# MCU_IO.net
KiCad netlist of a schematic drawn in Altium Designer
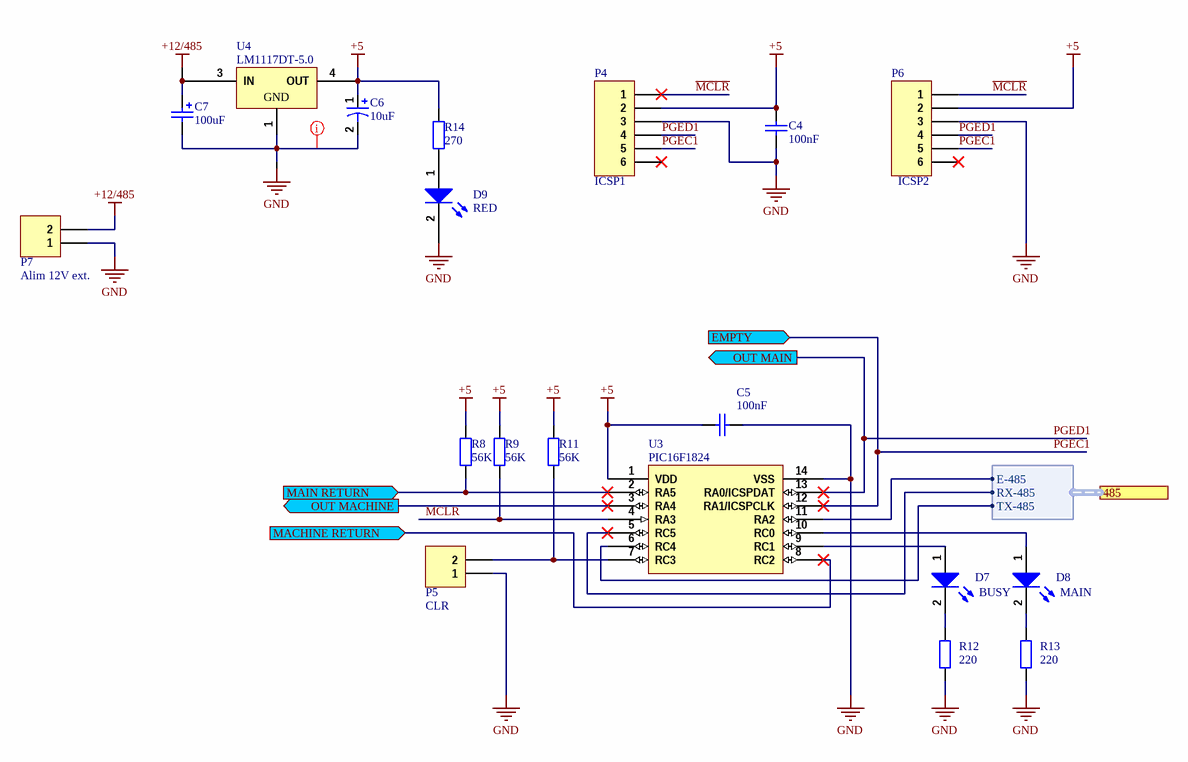
[diagram p0: MCU IO.SchDoc]

(export (version "E")
  (design (tool "Eeschema 10.0.6"))
  (components
    (comp (ref "C4")
      (value "100nF")
      (footprint "SYLANN:C0805")
      (description "Capacitor")
      (fields
        (field (name "MANUFACTURER") "MULTICOMP")
        (field (name "MANUFACTURER PART NUMBER") "MCCA000296")
      )
      (libsource (lib "Capacitors") (part "Cap 0805 100nF"))
    )
    (comp (ref "C5")
      (value "100nF")
      (footprint "SYLANN:C0805")
      (description "Capacitor")
      (fields
        (field (name "MANUFACTURER") "MULTICOMP")
        (field (name "MANUFACTURER PART NUMBER") "MCCA000296")
      )
      (libsource (lib "BRA") (part "Cap 0805 100nF"))
    )
    (comp (ref "C6")
      (value "10uF")
      (footprint "SYLANN:KEMET_4")
      (description "Polarized Capacitor")
      (fields
        (field (name "MANUFACTURER") "KEMET")
        (field (name "MANUFACTURER PART NUMBER") "EXV106M025A9BAA")
      )
      (libsource (lib "Miscellaneous Devices") (part "Cap Pol1"))
    )
    (comp (ref "C7")
      (value "100uF")
      (footprint "SYLANN:Kemet_63")
      (description "Polarized Capacitor")
      (fields
        (field (name "MANUFACTURER") "EPCOS")
        (field (name "MANUFACTURER PART NUMBER") "B41142A4107M")
        (field (name "HAUTEUR") "7.7")
        (field (name "LONGUEUR/HAUTEUR") "7.7")
      )
      (libsource (lib "BRA") (part "Cap Pol 100uF"))
    )
    (comp (ref "D7")
      (value "HSMH-C190")
      (footprint "0603-LEDR")
      (description "Surface Mount Chip LED, Red")
      (fields
        (field (name "MANUFACTURER") "AVAGO TECHNOLOGIES")
        (field (name "MANUFACTURER PART NUMBER") "HSMH-C190.")
        (field (name "INDICATOR") "BUSY")
        (field (name "LONGUEUR/HAUTEUR") "1.6")
      )
      (libsource (lib "BRA") (part "HSMH-C190"))
    )
    (comp (ref "D8")
      (value "HSMH-C190")
      (footprint "0603-LEDV")
      (description "Surface Mount Chip LED, Red")
      (fields
        (field (name "MANUFACTURER") "AVAGO TECHNOLOGIES")
        (field (name "MANUFACTURER PART NUMBER") "HSMH-C190.")
        (field (name "INDICATOR") "MAIN")
        (field (name "LONGUEUR/HAUTEUR") "1.6")
      )
      (libsource (lib "BRA") (part "HSMH-C190"))
    )
    (comp (ref "D9")
      (value "HSMH-C190")
      (footprint "0603-LEDR")
      (description "Surface Mount Chip LED, Red")
      (fields
        (field (name "MANUFACTURER") "AVAGO TECHNOLOGIES")
        (field (name "MANUFACTURER PART NUMBER") "HSMH-C190.")
        (field (name "COULEUR") "RED")
        (field (name "LONGUEUR/HAUTEUR") "1.6")
      )
      (libsource (lib "Avago Optoelectronic LED") (part "HSMH-C190"))
    )
    (comp (ref "P4")
      (value "ICSP1")
      (footprint "TC2030")
      (description "Header, 6-Pin")
      (fields (field (name "MANUFACTURER") "HARWIN") (field (name "MANUFACTURER PART NUMBER") "M20-8770642"))
      (libsource (lib "Miscellaneous Connectors") (part "Header 6"))
    )
    (comp (ref "P5")
      (value "CLR")
      (footprint "SYLANN:M20_1X2")
      (description "Header, 2-Pin")
      (fields
        (field (name "MANUFACTURER") "HARWIN")
        (field (name "MANUFACTURER PART NUMBER") "M20-8770242")
        (field (name "PUBLISHER") "Altium Limited")
      )
      (libsource (lib "Miscellaneous Connectors") (part "Header 2"))
    )
    (comp (ref "P6")
      (value "ICSP2")
      (footprint "6SIP100")
      (description "Header, 6-Pin")
      (fields
        (field (name "MANUFACTURER") "TE CONNECTIVITY / AMP")
        (field (name "MANUFACTURER PART NUMBER") "4-103321-8.")
      )
      (libsource (lib "Miscellaneous Connectors") (part "Header 6"))
    )
    (comp (ref "P7")
      (value "Alim 12V ext.")
      (footprint "CO2P508")
      (description "Header, 2-Pin")
      (libsource (lib "Miscellaneous Connectors") (part "Header 2"))
    )
    (comp (ref "R8")
      (value "56K")
      (footprint "R0805")
      (description "Resistor")
      (fields
        (field (name "MANUFACTURER") "MULTICOMP")
        (field (name "MANUFACTURER PART NUMBER") "MC0.1W08051%56KFR")
      )
      (libsource (lib "BRA") (part "Resistor 0805 56K"))
    )
    (comp (ref "R9")
      (value "56K")
      (footprint "R0805")
      (description "Resistor")
      (fields
        (field (name "MANUFACTURER") "MULTICOMP")
        (field (name "MANUFACTURER PART NUMBER") "MC0.1W08051%56KFR")
      )
      (libsource (lib "BRA") (part "Resistor 0805 56K"))
    )
    (comp (ref "R11")
      (value "56K")
      (footprint "R0805")
      (description "Resistor")
      (fields
        (field (name "MANUFACTURER") "MULTICOMP")
        (field (name "MANUFACTURER PART NUMBER") "MC0.1W08051%56KFR")
      )
      (libsource (lib "BRA") (part "Resistor 0805 56K"))
    )
    (comp (ref "R12")
      (value "220")
      (footprint "R0805")
      (description "Resistor")
      (fields
        (field (name "MANUFACTURER") "MULTICOMP")
        (field (name "MANUFACTURER PART NUMBER") "MC01W08051220R")
      )
      (libsource (lib "BRA") (part "Resistor 0805 220"))
    )
    (comp (ref "R13")
      (value "220")
      (footprint "R0805")
      (description "Resistor")
      (fields
        (field (name "MANUFACTURER") "MULTICOMP")
        (field (name "MANUFACTURER PART NUMBER") "MC01W08051220R")
      )
      (libsource (lib "BRA") (part "Resistor 0805 220"))
    )
    (comp (ref "R14")
      (value "270")
      (footprint "R0805")
      (description "Resistor")
      (fields
        (field (name "MANUFACTURER") "MULTICOMP")
        (field (name "MANUFACTURER PART NUMBER") "MC0.1W08051%1KFR")
      )
      (libsource (lib "BRA") (part "Resistor 0805 1K"))
    )
    (comp (ref "U3")
      (value "PIC16F1824")
      (footprint "so-14")
      (description "14 Pin Flash Microcontrollers with XLP Technology")
      (fields
        (field (name "MANUFACTURER") "MICROCHIP")
        (field (name "MANUFACTURER PART NUMBER") "PIC16F1824-I/SL")
      )
      (libsource (lib "BRA") (part "PIC16(L)F1824"))
    )
    (comp (ref "U4")
      (value "LM1117DT-5.0")
      (footprint "SOT223")
      (description "800mA Low-Dropout Linear Regulator, 3-pin TO-252")
      (fields
        (field (name "MANUFACTURER") "TEXAS INSTRUMENTS")
        (field (name "MANUFACTURER PART NUMBER") "LM1117MP-5.0")
      )
      (libsource (lib "NSC LDO") (part "LM1117DT-5.0"))
    )
  )
  (nets
    (net (code "2") (name "+5") (class "Default")
      (node (ref "C4") (pin "2") (pinfunction "2_2") (pintype "passive"))
      (node (ref "C5") (pin "2") (pinfunction "2_2") (pintype "passive"))
      (node (ref "C6") (pin "1") (pinfunction "1_1") (pintype "passive"))
      (node (ref "P4") (pin "2") (pinfunction "2_2") (pintype "passive"))
      (node (ref "P6") (pin "2") (pinfunction "2_2") (pintype "passive"))
      (node (ref "R11") (pin "2") (pinfunction "2_2") (pintype "passive"))
      (node (ref "R14") (pin "2") (pinfunction "2_2") (pintype "passive"))
      (node (ref "R8") (pin "2") (pinfunction "2_2") (pintype "passive"))
      (node (ref "R9") (pin "2") (pinfunction "2_2") (pintype "passive"))
      (node (ref "U3") (pin "1") (pinfunction "VDD_1") (pintype "power_in"))
      (node (ref "U4") (pin "4") (pinfunction "OUT_4") (pintype "power_in"))
    )
    (net (code "3") (name "+12{slash}485") (class "Default")
      (node (ref "C7") (pin "1") (pinfunction "1_1") (pintype "passive"))
      (node (ref "P7") (pin "2") (pinfunction "2_2") (pintype "passive"))
      (node (ref "U4") (pin "3") (pinfunction "IN_3") (pintype "power_in"))
    )
    (net (code "4") (name "/E-485") (class "Default")
      (node (ref "U3") (pin "11") (pinfunction "RA2_11") (pintype "bidirectional"))
    )
    (net (code "5") (name "/MACHINE RETURN") (class "Default")
      (node (ref "U3") (pin "8") (pinfunction "RC2_8") (pintype "bidirectional+no_connect"))
    )
    (net (code "6") (name "/MAIN RETURN") (class "Default")
      (node (ref "R8") (pin "1") (pinfunction "1_1") (pintype "passive"))
      (node (ref "U3") (pin "2") (pinfunction "RA5_2") (pintype "bidirectional"))
    )
    (net (code "7") (name "/OUT MACHINE") (class "Default")
      (node (ref "U3") (pin "3") (pinfunction "RA4_3") (pintype "bidirectional+no_connect"))
    )
    (net (code "8") (name "/PGEC1") (class "Default")
      (node (ref "P4") (pin "5") (pinfunction "5_5") (pintype "passive"))
      (node (ref "P6") (pin "5") (pinfunction "5_5") (pintype "passive"))
      (node (ref "U3") (pin "12") (pinfunction "RA1/ICSPCLK_12") (pintype "bidirectional"))
    )
    (net (code "9") (name "/PGED1") (class "Default")
      (node (ref "P4") (pin "4") (pinfunction "4_4") (pintype "passive"))
      (node (ref "P6") (pin "4") (pinfunction "4_4") (pintype "passive"))
      (node (ref "U3") (pin "13") (pinfunction "RA0/ICSPDAT_13") (pintype "bidirectional"))
    )
    (net (code "10") (name "/RX-485") (class "Default")
      (node (ref "U3") (pin "5") (pinfunction "RC5_5") (pintype "bidirectional+no_connect"))
    )
    (net (code "11") (name "/TX-485") (class "Default")
      (node (ref "U3") (pin "6") (pinfunction "RC4_6") (pintype "bidirectional"))
    )
    (net (code "13") (name "/~{MCLR}") (class "Default")
      (node (ref "P4") (pin "1") (pinfunction "1_1") (pintype "passive"))
      (node (ref "P6") (pin "1") (pinfunction "1_1") (pintype "passive"))
      (node (ref "R9") (pin "1") (pinfunction "1_1") (pintype "passive"))
      (node (ref "U3") (pin "4") (pinfunction "RA3_4") (pintype "input"))
    )
    (net (code "14") (name "GND") (class "Default")
      (node (ref "C4") (pin "1") (pinfunction "1_1") (pintype "passive"))
      (node (ref "C5") (pin "1") (pinfunction "1_1") (pintype "passive"))
      (node (ref "C6") (pin "2") (pinfunction "2_2") (pintype "passive"))
      (node (ref "C7") (pin "2") (pinfunction "2_2") (pintype "passive"))
      (node (ref "D9") (pin "2") (pinfunction "K_2") (pintype "passive"))
      (node (ref "P4") (pin "3") (pinfunction "3_3") (pintype "passive"))
      (node (ref "P5") (pin "1") (pinfunction "1_1") (pintype "passive"))
      (node (ref "P6") (pin "3") (pinfunction "3_3") (pintype "passive"))
      (node (ref "P7") (pin "1") (pinfunction "1_1") (pintype "passive"))
      (node (ref "R12") (pin "1") (pinfunction "1_1") (pintype "passive"))
      (node (ref "R13") (pin "1") (pinfunction "1_1") (pintype "passive"))
      (node (ref "U3") (pin "14") (pinfunction "VSS_14") (pintype "power_in"))
      (node (ref "U4") (pin "1") (pinfunction "GND_1") (pintype "power_in"))
    )
    (net (code "15") (name "Net-(D7-A)") (class "Default")
      (node (ref "D7") (pin "1") (pinfunction "A_1") (pintype "passive"))
      (node (ref "U3") (pin "9") (pinfunction "RC1_9") (pintype "bidirectional"))
    )
    (net (code "16") (name "Net-(D7-K)") (class "Default")
      (node (ref "D7") (pin "2") (pinfunction "K_2") (pintype "passive"))
      (node (ref "R12") (pin "2") (pinfunction "2_2") (pintype "passive"))
    )
    (net (code "17") (name "Net-(D8-A)") (class "Default")
      (node (ref "D8") (pin "1") (pinfunction "A_1") (pintype "passive"))
      (node (ref "U3") (pin "10") (pinfunction "RC0_10") (pintype "bidirectional"))
    )
    (net (code "18") (name "Net-(D8-K)") (class "Default")
      (node (ref "D8") (pin "2") (pinfunction "K_2") (pintype "passive"))
      (node (ref "R13") (pin "2") (pinfunction "2_2") (pintype "passive"))
    )
    (net (code "19") (name "Net-(D9-A)") (class "Default")
      (node (ref "D9") (pin "1") (pinfunction "A_1") (pintype "passive"))
      (node (ref "R14") (pin "1") (pinfunction "1_1") (pintype "passive"))
    )
    (net (code "20") (name "Net-(U3-RC3)") (class "Default")
      (node (ref "P5") (pin "2") (pinfunction "2_2") (pintype "passive"))
      (node (ref "R11") (pin "1") (pinfunction "1_1") (pintype "passive"))
      (node (ref "U3") (pin "7") (pinfunction "RC3_7") (pintype "bidirectional"))
    )
    (net (code "21") (name "unconnected-(P4-Pad6)") (class "Default")
      (node (ref "P4") (pin "6") (pinfunction "6_6") (pintype "passive+no_connect"))
    )
    (net (code "22") (name "unconnected-(P6-Pad6)") (class "Default")
      (node (ref "P6") (pin "6") (pinfunction "6_6") (pintype "passive+no_connect"))
    )
  )
)
